# PWRInput.net
KiCad netlist of a schematic drawn in Altium Designer
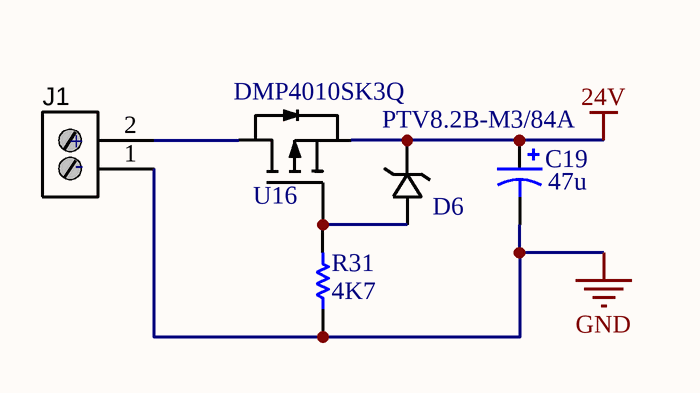
[diagram p0: PWRInput.SchDoc]

(export (version "E")
  (design (tool "Eeschema 10.0.6"))
  (components
    (comp (ref "C19")
      (value "47u")
      (footprint "CAP_ELEC_5x5.7")
      (description "Polarized Capacitor (Radial)")
      (fields (field (name "Comment") "Cap Pol1") (field (name "PUBLISHER") "Altium Limited"))
      (libsource (lib "Miscellaneous Devices") (part "Cap Pol1"))
    )
    (comp (ref "D6")
      (value "PTV8.2B-M3/84A")
      (footprint "DO-220AA")
      (description "zener diode, Surface Mount Power Voltage-Regulating Diodes")
      (fields (field (name "MANUFACTURER") "Vishay"))
      (libsource (lib "IOBoard_Low") (part "PTV8.2B-M3/84A"))
    )
    (comp (ref "J1")
      (value "Stackable ScrewTerm")
      (footprint "2P_PCB_TERM")
      (description "Terminal Block Screw Type THT 2-Position 3.81mm pitch")
      (libsource (lib "IOBoard_Low") (part "2P_ScrewTerm_90S_3.81MM"))
    )
    (comp (ref "R31")
      (value "4K7")
      (footprint "RESC1608X55N")
      (description "Resistor")
      (fields (field (name "Comment") "Res1") (field (name "PUBLISHER") "Altium Limited"))
      (libsource (lib "IOBoard_Low") (part "Res1"))
    )
    (comp (ref "U16")
      (value "DMP4010SK3Q")
      (footprint "TO-252")
      (libsource (lib "IOBoard_Low") (part "DMP4010SK3Q"))
    )
  )
  (nets
    (net (code "1") (name "24V") (class "Default")
      (node (ref "C19") (pin "1") (pinfunction "1_1") (pintype "passive"))
      (node (ref "D6") (pin "K") (pinfunction "K_K") (pintype "passive"))
      (node (ref "U16") (pin "3") (pinfunction "S_3") (pintype "passive"))
    )
    (net (code "2") (name "GND") (class "Default")
      (node (ref "C19") (pin "2") (pinfunction "2_2") (pintype "passive"))
      (node (ref "J1") (pin "1") (pinfunction "1_1") (pintype "passive"))
      (node (ref "R31") (pin "1") (pinfunction "1_1") (pintype "passive"))
    )
    (net (code "3") (name "Net-(U16-D)") (class "Default")
      (node (ref "J1") (pin "2") (pinfunction "2_2") (pintype "passive"))
      (node (ref "U16") (pin "4") (pinfunction "D_4") (pintype "passive"))
    )
    (net (code "4") (name "Net-(U16-G)") (class "Default")
      (node (ref "D6") (pin "A") (pinfunction "A_A") (pintype "passive"))
      (node (ref "R31") (pin "2") (pinfunction "2_2") (pintype "passive"))
      (node (ref "U16") (pin "1") (pinfunction "G_1") (pintype "passive"))
    )
  )
)
